# LoRa-E5-Breakout.net
KiCad netlist of a schematic drawn in EAGLE
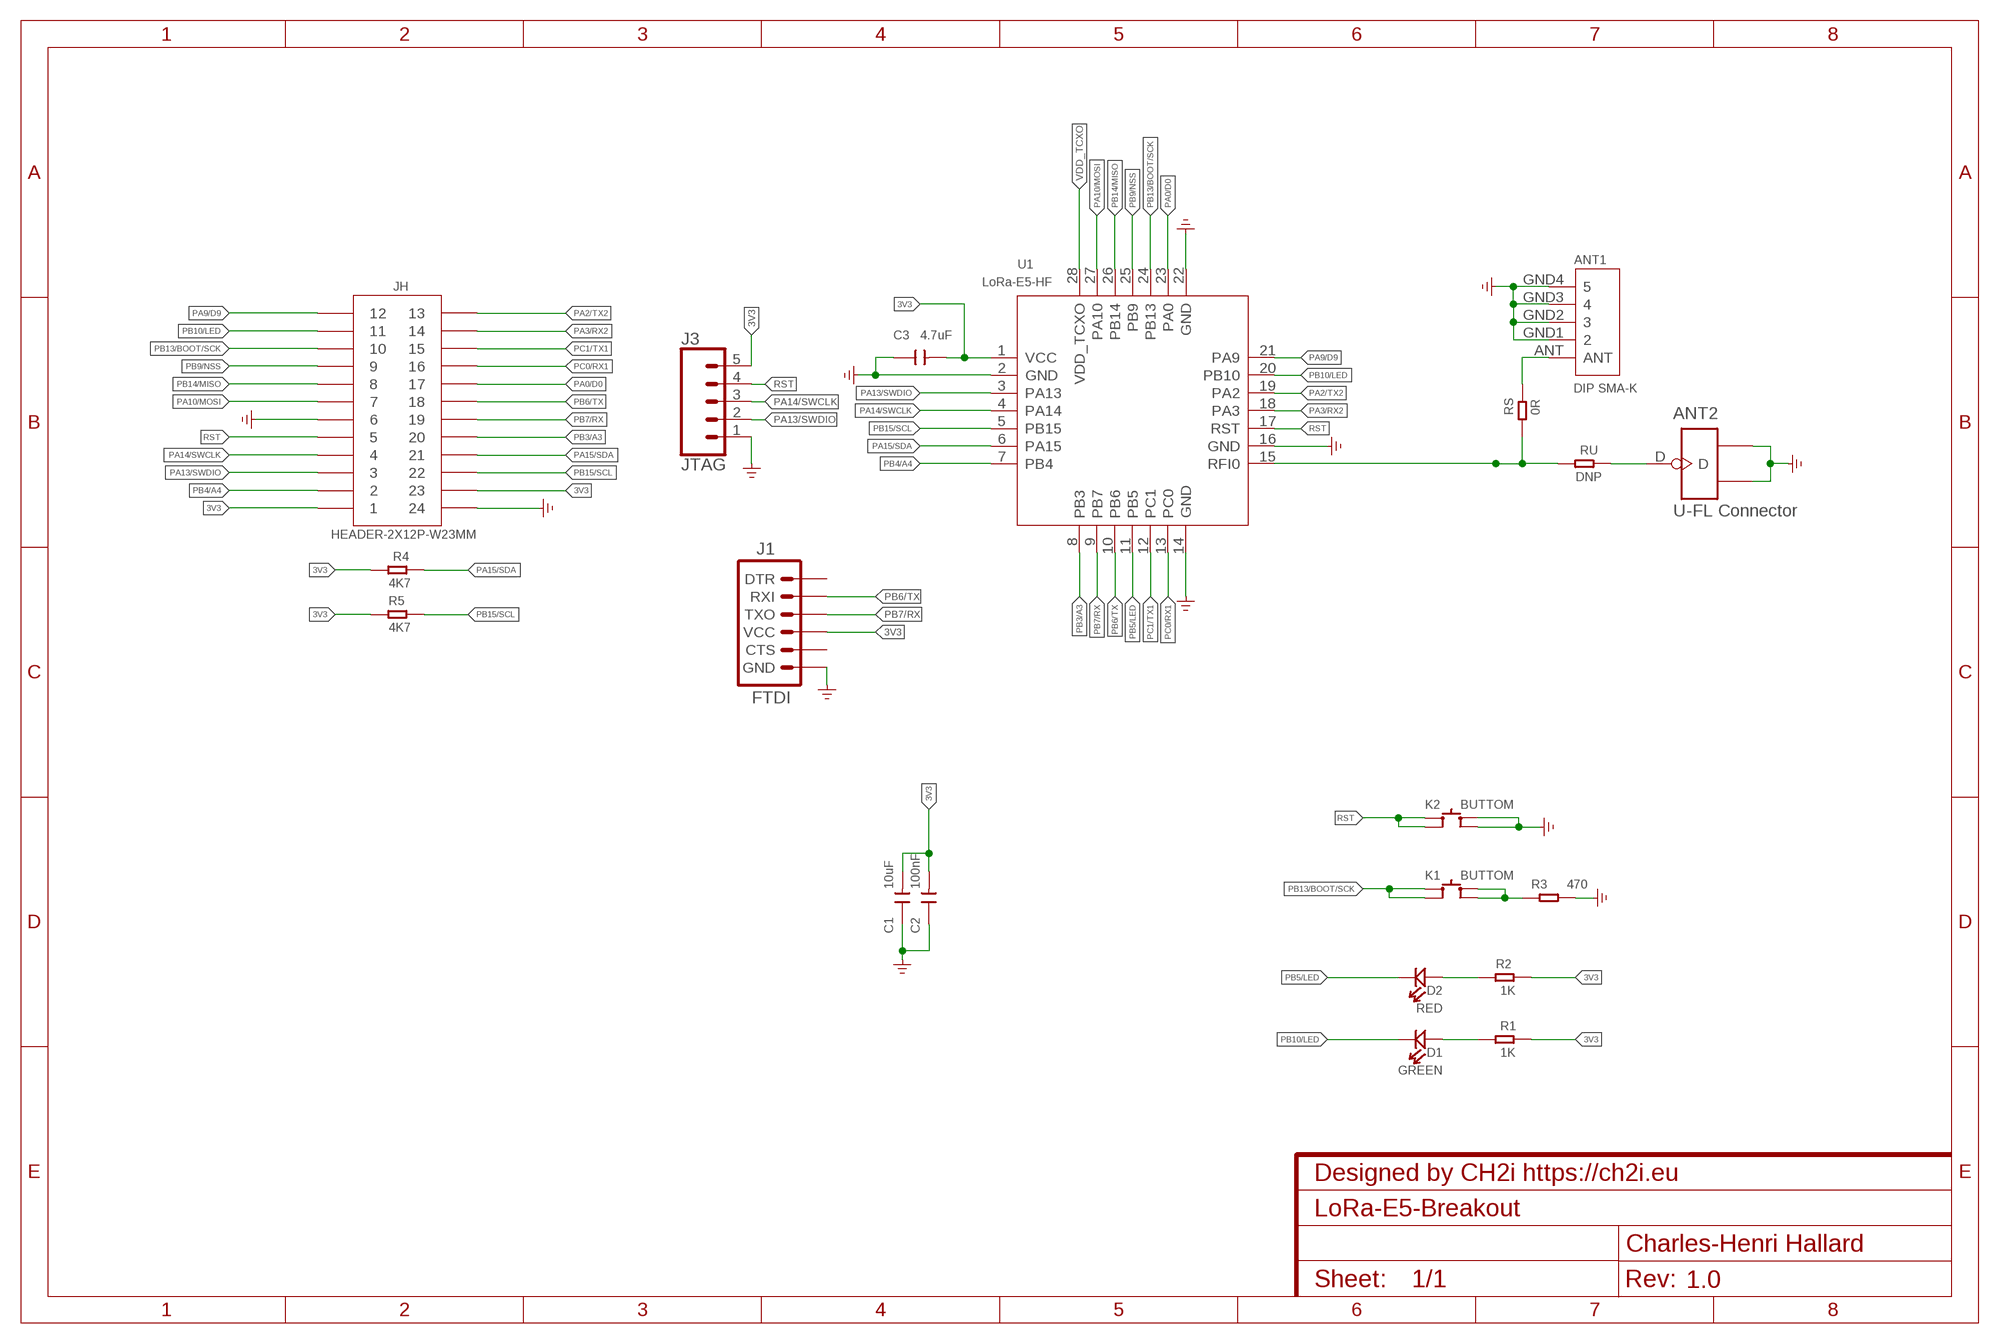
[diagram p0: schematic, sheet 1]

(export (version "E")
  (design (tool "Eeschema 10.0.6"))
  (components
    (comp (ref "ANT1")
      (value "DIP SMA-K")
      (footprint "eagle-import:SMA5P-SMD-5.1-6.5X6.5X16.5MM")
      (libsource (lib "eagle-import") (part "ANTENNA-SMA-MCX-JE-320160125"))
    )
    (comp (ref "ANT2")
      (value "U-FL Connector")
      (footprint "eagle-import:U-FL3P-SMD-2.6X2.6X1.0MM")
      (libsource (lib "eagle-import") (part "ANTENNA-U-FL-320110048"))
    )
    (comp (ref "C1")
      (value "10uF")
      (footprint "eagle-import:C0805")
      (libsource (lib "eagle-import") (part "CAP-0805"))
    )
    (comp (ref "C2")
      (value "100nF")
      (footprint "eagle-import:C0805")
      (libsource (lib "eagle-import") (part "CAP-0805"))
    )
    (comp (ref "C3")
      (value "4.7uF")
      (footprint "eagle-import:C0805")
      (libsource (lib "eagle-import") (part "CAP-0805"))
    )
    (comp (ref "D1")
      (value "GREEN")
      (footprint "eagle-import:LED-0805")
      (libsource (lib "eagle-import") (part "LED'0805'"))
    )
    (comp (ref "D2")
      (value "RED")
      (footprint "eagle-import:LED-0805")
      (libsource (lib "eagle-import") (part "LED'0805'"))
    )
    (comp (ref "J1")
      (value "FTDI")
      (footprint "eagle-import:1X06-SMD_RA_MALE")
      (libsource (lib "eagle-import") (part "6_PIN_SERIAL_TARGETSMD"))
    )
    (comp (ref "J3")
      (value "JTAG")
      (footprint "eagle-import:1X05_LOCK")
      (libsource (lib "eagle-import") (part "CONN_05LOCK"))
    )
    (comp (ref "JH")
      (value "HEADER-2X12P-W23MM")
      (footprint "eagle-import:H2X12-2.54-23MM")
      (libsource (lib "eagle-import") (part "HEADER-2X12P-W23MM"))
    )
    (comp (ref "K1")
      (value "BUTTOM")
      (footprint "eagle-import:SW4P-SMD-4.5X3.2X2.5MM")
      (libsource (lib "eagle-import") (part "BUTTON-4P-4.5X3.2"))
    )
    (comp (ref "K2")
      (value "BUTTOM")
      (footprint "eagle-import:SW4P-SMD-4.5X3.2X2.5MM")
      (libsource (lib "eagle-import") (part "BUTTON-4P-4.5X3.2"))
    )
    (comp (ref "R1")
      (value "1K")
      (footprint "eagle-import:R0805")
      (libsource (lib "eagle-import") (part "RES-0805"))
    )
    (comp (ref "R2")
      (value "1K")
      (footprint "eagle-import:R0805")
      (libsource (lib "eagle-import") (part "RES-0805"))
    )
    (comp (ref "R3")
      (value "470")
      (footprint "eagle-import:R0805")
      (libsource (lib "eagle-import") (part "RES-0805"))
    )
    (comp (ref "R4")
      (value "4K7")
      (footprint "eagle-import:R0805")
      (libsource (lib "eagle-import") (part "RES-0805"))
    )
    (comp (ref "R5")
      (value "4K7")
      (footprint "eagle-import:R0805")
      (libsource (lib "eagle-import") (part "RES-0805"))
    )
    (comp (ref "RS")
      (value "0R")
      (footprint "eagle-import:R0603")
      (libsource (lib "eagle-import") (part "RES-0603"))
    )
    (comp (ref "RU")
      (value "DNP")
      (footprint "eagle-import:R0603")
      (libsource (lib "eagle-import") (part "RES-0603"))
    )
    (comp (ref "U1")
      (value "LoRa-E5-HF")
      (footprint "eagle-import:MOUDLE28P-1.25-12X12X2.5MM")
      (libsource (lib "eagle-import") (part "MOUDLE_LORA_E5"))
    )
  )
  (nets
    (net (code "1") (name "3V3") (class "Default")
      (node (ref "C1") (pin "2") (pinfunction "2_2") (pintype "passive"))
      (node (ref "C2") (pin "2") (pinfunction "2_2") (pintype "passive"))
      (node (ref "C3") (pin "2") (pinfunction "2_2") (pintype "passive"))
      (node (ref "J1") (pin "4") (pinfunction "VCC_4") (pintype "passive"))
      (node (ref "J3") (pin "5") (pinfunction "5_5") (pintype "passive"))
      (node (ref "JH") (pin "A1") (pinfunction "1_A1") (pintype "bidirectional"))
      (node (ref "JH") (pin "B1") (pinfunction "1_B1") (pintype "bidirectional"))
      (node (ref "JH") (pin "C11") (pinfunction "23_C11") (pintype "bidirectional"))
      (node (ref "JH") (pin "D11") (pinfunction "23_D11") (pintype "bidirectional"))
      (node (ref "JH") (pin "E1") (pinfunction "1_E1") (pintype "bidirectional"))
      (node (ref "JH") (pin "E23") (pinfunction "23_E23") (pintype "bidirectional"))
      (node (ref "JH") (pin "F1") (pinfunction "1_F1") (pintype "bidirectional"))
      (node (ref "JH") (pin "F23") (pinfunction "23_F23") (pintype "bidirectional"))
      (node (ref "R1") (pin "2") (pinfunction "2_2") (pintype "passive"))
      (node (ref "R2") (pin "2") (pinfunction "2_2") (pintype "passive"))
      (node (ref "R4") (pin "1") (pinfunction "1_1") (pintype "passive"))
      (node (ref "R5") (pin "1") (pinfunction "1_1") (pintype "passive"))
      (node (ref "U1") (pin "1") (pinfunction "VCC_1") (pintype "bidirectional"))
    )
    (net (code "2") (name "GND_POWER") (class "Default")
      (node (ref "ANT1") (pin "GND1") (pinfunction "2_GND1") (pintype "bidirectional"))
      (node (ref "ANT1") (pin "GND2") (pinfunction "3_GND2") (pintype "bidirectional"))
      (node (ref "ANT1") (pin "GND3") (pinfunction "4_GND3") (pintype "bidirectional"))
      (node (ref "ANT1") (pin "GND4") (pinfunction "5_GND4") (pintype "bidirectional"))
      (node (ref "ANT2") (pin "GND1") (pinfunction "GND1_GND1") (pintype "bidirectional"))
      (node (ref "ANT2") (pin "GND2") (pinfunction "GND2_GND2") (pintype "bidirectional"))
      (node (ref "C1") (pin "1") (pinfunction "1_1") (pintype "passive"))
      (node (ref "C2") (pin "1") (pinfunction "1_1") (pintype "passive"))
      (node (ref "C3") (pin "1") (pinfunction "1_1") (pintype "passive"))
      (node (ref "J1") (pin "6") (pinfunction "GND_6") (pintype "passive"))
      (node (ref "J3") (pin "1") (pinfunction "1_1") (pintype "passive"))
      (node (ref "JH") (pin "A6") (pinfunction "6_A6") (pintype "bidirectional"))
      (node (ref "JH") (pin "B6") (pinfunction "6_B6") (pintype "bidirectional"))
      (node (ref "JH") (pin "C12") (pinfunction "24_C12") (pintype "bidirectional"))
      (node (ref "JH") (pin "D12") (pinfunction "24_D12") (pintype "bidirectional"))
      (node (ref "JH") (pin "E24") (pinfunction "24_E24") (pintype "bidirectional"))
      (node (ref "JH") (pin "E6") (pinfunction "6_E6") (pintype "bidirectional"))
      (node (ref "JH") (pin "F24") (pinfunction "24_F24") (pintype "bidirectional"))
      (node (ref "JH") (pin "F6") (pinfunction "6_F6") (pintype "bidirectional"))
      (node (ref "K2") (pin "3") (pinfunction "B0_3") (pintype "bidirectional"))
      (node (ref "K2") (pin "4") (pinfunction "B1_4") (pintype "bidirectional"))
      (node (ref "R3") (pin "2") (pinfunction "2_2") (pintype "passive"))
      (node (ref "U1") (pin "14") (pinfunction "GND_14") (pintype "bidirectional"))
      (node (ref "U1") (pin "16") (pinfunction "GND_16") (pintype "bidirectional"))
      (node (ref "U1") (pin "2") (pinfunction "GND_2") (pintype "bidirectional"))
      (node (ref "U1") (pin "22") (pinfunction "GND_22") (pintype "bidirectional"))
    )
    (net (code "3") (name "Net-(ANT1-PadANT)") (class "Default")
      (node (ref "ANT1") (pin "ANT") (pinfunction "ANT_ANT") (pintype "bidirectional"))
      (node (ref "RS") (pin "2") (pinfunction "2_2") (pintype "passive"))
    )
    (net (code "4") (name "Net-(ANT2-PadD)") (class "Default")
      (node (ref "ANT2") (pin "D") (pinfunction "D_D") (pintype "bidirectional"))
      (node (ref "RU") (pin "2") (pinfunction "2_2") (pintype "passive"))
    )
    (net (code "5") (name "Net-(D1-Pad+)") (class "Default")
      (node (ref "D1") (pin "+") (pinfunction "+_+") (pintype "passive"))
      (node (ref "R1") (pin "1") (pinfunction "1_1") (pintype "passive"))
    )
    (net (code "6") (name "Net-(D2-Pad+)") (class "Default")
      (node (ref "D2") (pin "+") (pinfunction "+_+") (pintype "passive"))
      (node (ref "R2") (pin "1") (pinfunction "1_1") (pintype "passive"))
    )
    (net (code "7") (name "Net-(K1-B0)") (class "Default")
      (node (ref "K1") (pin "3") (pinfunction "B0_3") (pintype "bidirectional"))
      (node (ref "K1") (pin "4") (pinfunction "B1_4") (pintype "bidirectional"))
      (node (ref "R3") (pin "1") (pinfunction "1_1") (pintype "passive"))
    )
    (net (code "8") (name "Net-(U1-RFI0)") (class "Default")
      (node (ref "RS") (pin "1") (pinfunction "1_1") (pintype "passive"))
      (node (ref "RU") (pin "1") (pinfunction "1_1") (pintype "passive"))
      (node (ref "U1") (pin "15") (pinfunction "RFI0_15") (pintype "bidirectional"))
    )
    (net (code "9") (name "PA0{slash}D0") (class "Default")
      (node (ref "JH") (pin "C5") (pinfunction "17_C5") (pintype "bidirectional"))
      (node (ref "JH") (pin "D5") (pinfunction "17_D5") (pintype "bidirectional"))
      (node (ref "JH") (pin "E17") (pinfunction "17_E17") (pintype "bidirectional"))
      (node (ref "JH") (pin "F17") (pinfunction "17_F17") (pintype "bidirectional"))
      (node (ref "U1") (pin "23") (pinfunction "PA0_23") (pintype "bidirectional"))
    )
    (net (code "10") (name "PA2{slash}TX2") (class "Default")
      (node (ref "JH") (pin "C1") (pinfunction "13_C1") (pintype "bidirectional"))
      (node (ref "JH") (pin "D1") (pinfunction "13_D1") (pintype "bidirectional"))
      (node (ref "JH") (pin "E13") (pinfunction "13_E13") (pintype "bidirectional"))
      (node (ref "JH") (pin "F13") (pinfunction "13_F13") (pintype "bidirectional"))
      (node (ref "U1") (pin "19") (pinfunction "PA2_19") (pintype "bidirectional"))
    )
    (net (code "11") (name "PA3{slash}RX2") (class "Default")
      (node (ref "JH") (pin "C2") (pinfunction "14_C2") (pintype "bidirectional"))
      (node (ref "JH") (pin "D2") (pinfunction "14_D2") (pintype "bidirectional"))
      (node (ref "JH") (pin "E14") (pinfunction "14_E14") (pintype "bidirectional"))
      (node (ref "JH") (pin "F14") (pinfunction "14_F14") (pintype "bidirectional"))
      (node (ref "U1") (pin "18") (pinfunction "PA3_18") (pintype "bidirectional"))
    )
    (net (code "12") (name "PA9{slash}D9") (class "Default")
      (node (ref "JH") (pin "A12") (pinfunction "12_A12") (pintype "bidirectional"))
      (node (ref "JH") (pin "B12") (pinfunction "12_B12") (pintype "bidirectional"))
      (node (ref "JH") (pin "E12") (pinfunction "12_E12") (pintype "bidirectional"))
      (node (ref "JH") (pin "F12") (pinfunction "12_F12") (pintype "bidirectional"))
      (node (ref "U1") (pin "21") (pinfunction "PA9_21") (pintype "bidirectional"))
    )
    (net (code "13") (name "PA10{slash}MOSI") (class "Default")
      (node (ref "JH") (pin "A7") (pinfunction "7_A7") (pintype "bidirectional"))
      (node (ref "JH") (pin "B7") (pinfunction "7_B7") (pintype "bidirectional"))
      (node (ref "JH") (pin "E7") (pinfunction "7_E7") (pintype "bidirectional"))
      (node (ref "JH") (pin "F7") (pinfunction "7_F7") (pintype "bidirectional"))
      (node (ref "U1") (pin "27") (pinfunction "PA10_27") (pintype "bidirectional"))
    )
    (net (code "14") (name "PA13{slash}SWDIO") (class "Default")
      (node (ref "J3") (pin "2") (pinfunction "2_2") (pintype "passive"))
      (node (ref "JH") (pin "A3") (pinfunction "3_A3") (pintype "bidirectional"))
      (node (ref "JH") (pin "B3") (pinfunction "3_B3") (pintype "bidirectional"))
      (node (ref "JH") (pin "E3") (pinfunction "3_E3") (pintype "bidirectional"))
      (node (ref "JH") (pin "F3") (pinfunction "3_F3") (pintype "bidirectional"))
      (node (ref "U1") (pin "3") (pinfunction "PA13_3") (pintype "bidirectional"))
    )
    (net (code "15") (name "PA14{slash}SWCLK") (class "Default")
      (node (ref "J3") (pin "3") (pinfunction "3_3") (pintype "passive"))
      (node (ref "JH") (pin "A4") (pinfunction "4_A4") (pintype "bidirectional"))
      (node (ref "JH") (pin "B4") (pinfunction "4_B4") (pintype "bidirectional"))
      (node (ref "JH") (pin "E4") (pinfunction "4_E4") (pintype "bidirectional"))
      (node (ref "JH") (pin "F4") (pinfunction "4_F4") (pintype "bidirectional"))
      (node (ref "U1") (pin "4") (pinfunction "PA14_4") (pintype "bidirectional"))
    )
    (net (code "16") (name "PA15{slash}SDA") (class "Default")
      (node (ref "JH") (pin "C9") (pinfunction "21_C9") (pintype "bidirectional"))
      (node (ref "JH") (pin "D9") (pinfunction "21_D9") (pintype "bidirectional"))
      (node (ref "JH") (pin "E21") (pinfunction "21_E21") (pintype "bidirectional"))
      (node (ref "JH") (pin "F21") (pinfunction "21_F21") (pintype "bidirectional"))
      (node (ref "R4") (pin "2") (pinfunction "2_2") (pintype "passive"))
      (node (ref "U1") (pin "6") (pinfunction "PA15_6") (pintype "bidirectional"))
    )
    (net (code "17") (name "PB3{slash}A3") (class "Default")
      (node (ref "JH") (pin "C8") (pinfunction "20_C8") (pintype "bidirectional"))
      (node (ref "JH") (pin "D8") (pinfunction "20_D8") (pintype "bidirectional"))
      (node (ref "JH") (pin "E20") (pinfunction "20_E20") (pintype "bidirectional"))
      (node (ref "JH") (pin "F20") (pinfunction "20_F20") (pintype "bidirectional"))
      (node (ref "U1") (pin "8") (pinfunction "PB3_8") (pintype "bidirectional"))
    )
    (net (code "18") (name "PB4{slash}A4") (class "Default")
      (node (ref "JH") (pin "A2") (pinfunction "2_A2") (pintype "bidirectional"))
      (node (ref "JH") (pin "B2") (pinfunction "2_B2") (pintype "bidirectional"))
      (node (ref "JH") (pin "E2") (pinfunction "2_E2") (pintype "bidirectional"))
      (node (ref "JH") (pin "F2") (pinfunction "2_F2") (pintype "bidirectional"))
      (node (ref "U1") (pin "7") (pinfunction "PB4_7") (pintype "bidirectional"))
    )
    (net (code "19") (name "PB5{slash}LED") (class "Default")
      (node (ref "D2") (pin "-") (pinfunction "-_-") (pintype "passive"))
      (node (ref "U1") (pin "11") (pinfunction "PB5_11") (pintype "bidirectional"))
    )
    (net (code "20") (name "PB6{slash}TX") (class "Default")
      (node (ref "J1") (pin "2") (pinfunction "RXI_2") (pintype "passive"))
      (node (ref "JH") (pin "C6") (pinfunction "18_C6") (pintype "bidirectional"))
      (node (ref "JH") (pin "D6") (pinfunction "18_D6") (pintype "bidirectional"))
      (node (ref "JH") (pin "E18") (pinfunction "18_E18") (pintype "bidirectional"))
      (node (ref "JH") (pin "F18") (pinfunction "18_F18") (pintype "bidirectional"))
      (node (ref "U1") (pin "10") (pinfunction "PB6_10") (pintype "bidirectional"))
    )
    (net (code "21") (name "PB7{slash}RX") (class "Default")
      (node (ref "J1") (pin "3") (pinfunction "TXO_3") (pintype "passive"))
      (node (ref "JH") (pin "C7") (pinfunction "19_C7") (pintype "bidirectional"))
      (node (ref "JH") (pin "D7") (pinfunction "19_D7") (pintype "bidirectional"))
      (node (ref "JH") (pin "E19") (pinfunction "19_E19") (pintype "bidirectional"))
      (node (ref "JH") (pin "F19") (pinfunction "19_F19") (pintype "bidirectional"))
      (node (ref "U1") (pin "9") (pinfunction "PB7_9") (pintype "bidirectional"))
    )
    (net (code "22") (name "PB9{slash}NSS") (class "Default")
      (node (ref "JH") (pin "A9") (pinfunction "9_A9") (pintype "bidirectional"))
      (node (ref "JH") (pin "B9") (pinfunction "9_B9") (pintype "bidirectional"))
      (node (ref "JH") (pin "E9") (pinfunction "9_E9") (pintype "bidirectional"))
      (node (ref "JH") (pin "F9") (pinfunction "9_F9") (pintype "bidirectional"))
      (node (ref "U1") (pin "25") (pinfunction "PB9_25") (pintype "bidirectional"))
    )
    (net (code "23") (name "PB10{slash}LED") (class "Default")
      (node (ref "D1") (pin "-") (pinfunction "-_-") (pintype "passive"))
      (node (ref "JH") (pin "A11") (pinfunction "11_A11") (pintype "bidirectional"))
      (node (ref "JH") (pin "B11") (pinfunction "11_B11") (pintype "bidirectional"))
      (node (ref "JH") (pin "E11") (pinfunction "11_E11") (pintype "bidirectional"))
      (node (ref "JH") (pin "F11") (pinfunction "11_F11") (pintype "bidirectional"))
      (node (ref "U1") (pin "20") (pinfunction "PB10_20") (pintype "bidirectional"))
    )
    (net (code "24") (name "PB13{slash}BOOT{slash}SCK") (class "Default")
      (node (ref "JH") (pin "A10") (pinfunction "10_A10") (pintype "bidirectional"))
      (node (ref "JH") (pin "B10") (pinfunction "10_B10") (pintype "bidirectional"))
      (node (ref "JH") (pin "E10") (pinfunction "10_E10") (pintype "bidirectional"))
      (node (ref "JH") (pin "F10") (pinfunction "10_F10") (pintype "bidirectional"))
      (node (ref "K1") (pin "1") (pinfunction "A0_1") (pintype "bidirectional"))
      (node (ref "K1") (pin "2") (pinfunction "A1_2") (pintype "bidirectional"))
      (node (ref "U1") (pin "24") (pinfunction "PB13_24") (pintype "bidirectional"))
    )
    (net (code "25") (name "PB14{slash}MISO") (class "Default")
      (node (ref "JH") (pin "A8") (pinfunction "8_A8") (pintype "bidirectional"))
      (node (ref "JH") (pin "B8") (pinfunction "8_B8") (pintype "bidirectional"))
      (node (ref "JH") (pin "E8") (pinfunction "8_E8") (pintype "bidirectional"))
      (node (ref "JH") (pin "F8") (pinfunction "8_F8") (pintype "bidirectional"))
      (node (ref "U1") (pin "26") (pinfunction "PB14_26") (pintype "bidirectional"))
    )
    (net (code "26") (name "PB15{slash}SCL") (class "Default")
      (node (ref "JH") (pin "C10") (pinfunction "22_C10") (pintype "bidirectional"))
      (node (ref "JH") (pin "D10") (pinfunction "22_D10") (pintype "bidirectional"))
      (node (ref "JH") (pin "E22") (pinfunction "22_E22") (pintype "bidirectional"))
      (node (ref "JH") (pin "F22") (pinfunction "22_F22") (pintype "bidirectional"))
      (node (ref "R5") (pin "2") (pinfunction "2_2") (pintype "passive"))
      (node (ref "U1") (pin "5") (pinfunction "PB15_5") (pintype "bidirectional"))
    )
    (net (code "27") (name "PC0{slash}RX1") (class "Default")
      (node (ref "JH") (pin "C4") (pinfunction "16_C4") (pintype "bidirectional"))
      (node (ref "JH") (pin "D4") (pinfunction "16_D4") (pintype "bidirectional"))
      (node (ref "JH") (pin "E16") (pinfunction "16_E16") (pintype "bidirectional"))
      (node (ref "JH") (pin "F16") (pinfunction "16_F16") (pintype "bidirectional"))
      (node (ref "U1") (pin "13") (pinfunction "PC0_13") (pintype "bidirectional"))
    )
    (net (code "28") (name "PC1{slash}TX1") (class "Default")
      (node (ref "JH") (pin "C3") (pinfunction "15_C3") (pintype "bidirectional"))
      (node (ref "JH") (pin "D3") (pinfunction "15_D3") (pintype "bidirectional"))
      (node (ref "JH") (pin "E15") (pinfunction "15_E15") (pintype "bidirectional"))
      (node (ref "JH") (pin "F15") (pinfunction "15_F15") (pintype "bidirectional"))
      (node (ref "U1") (pin "12") (pinfunction "PC1_12") (pintype "bidirectional"))
    )
    (net (code "29") (name "RST") (class "Default")
      (node (ref "J3") (pin "4") (pinfunction "4_4") (pintype "passive"))
      (node (ref "JH") (pin "A5") (pinfunction "5_A5") (pintype "bidirectional"))
      (node (ref "JH") (pin "B5") (pinfunction "5_B5") (pintype "bidirectional"))
      (node (ref "JH") (pin "E5") (pinfunction "5_E5") (pintype "bidirectional"))
      (node (ref "JH") (pin "F5") (pinfunction "5_F5") (pintype "bidirectional"))
      (node (ref "K2") (pin "1") (pinfunction "A0_1") (pintype "bidirectional"))
      (node (ref "K2") (pin "2") (pinfunction "A1_2") (pintype "bidirectional"))
      (node (ref "U1") (pin "17") (pinfunction "RST_17") (pintype "bidirectional"))
    )
    (net (code "30") (name "VDD_TCXO") (class "Default")
      (node (ref "U1") (pin "28") (pinfunction "VDD_TCXO_28") (pintype "bidirectional"))
    )
    (net (code "31") (name "unconnected-(J1-CTS-Pad5)") (class "Default")
      (node (ref "J1") (pin "5") (pinfunction "CTS_5") (pintype "passive"))
    )
    (net (code "32") (name "unconnected-(J1-DTR-Pad1)") (class "Default")
      (node (ref "J1") (pin "1") (pinfunction "DTR_1") (pintype "passive"))
    )
  )
)
